# TIDA-01485_Page3.net
KiCad netlist of a schematic drawn in Altium Designer
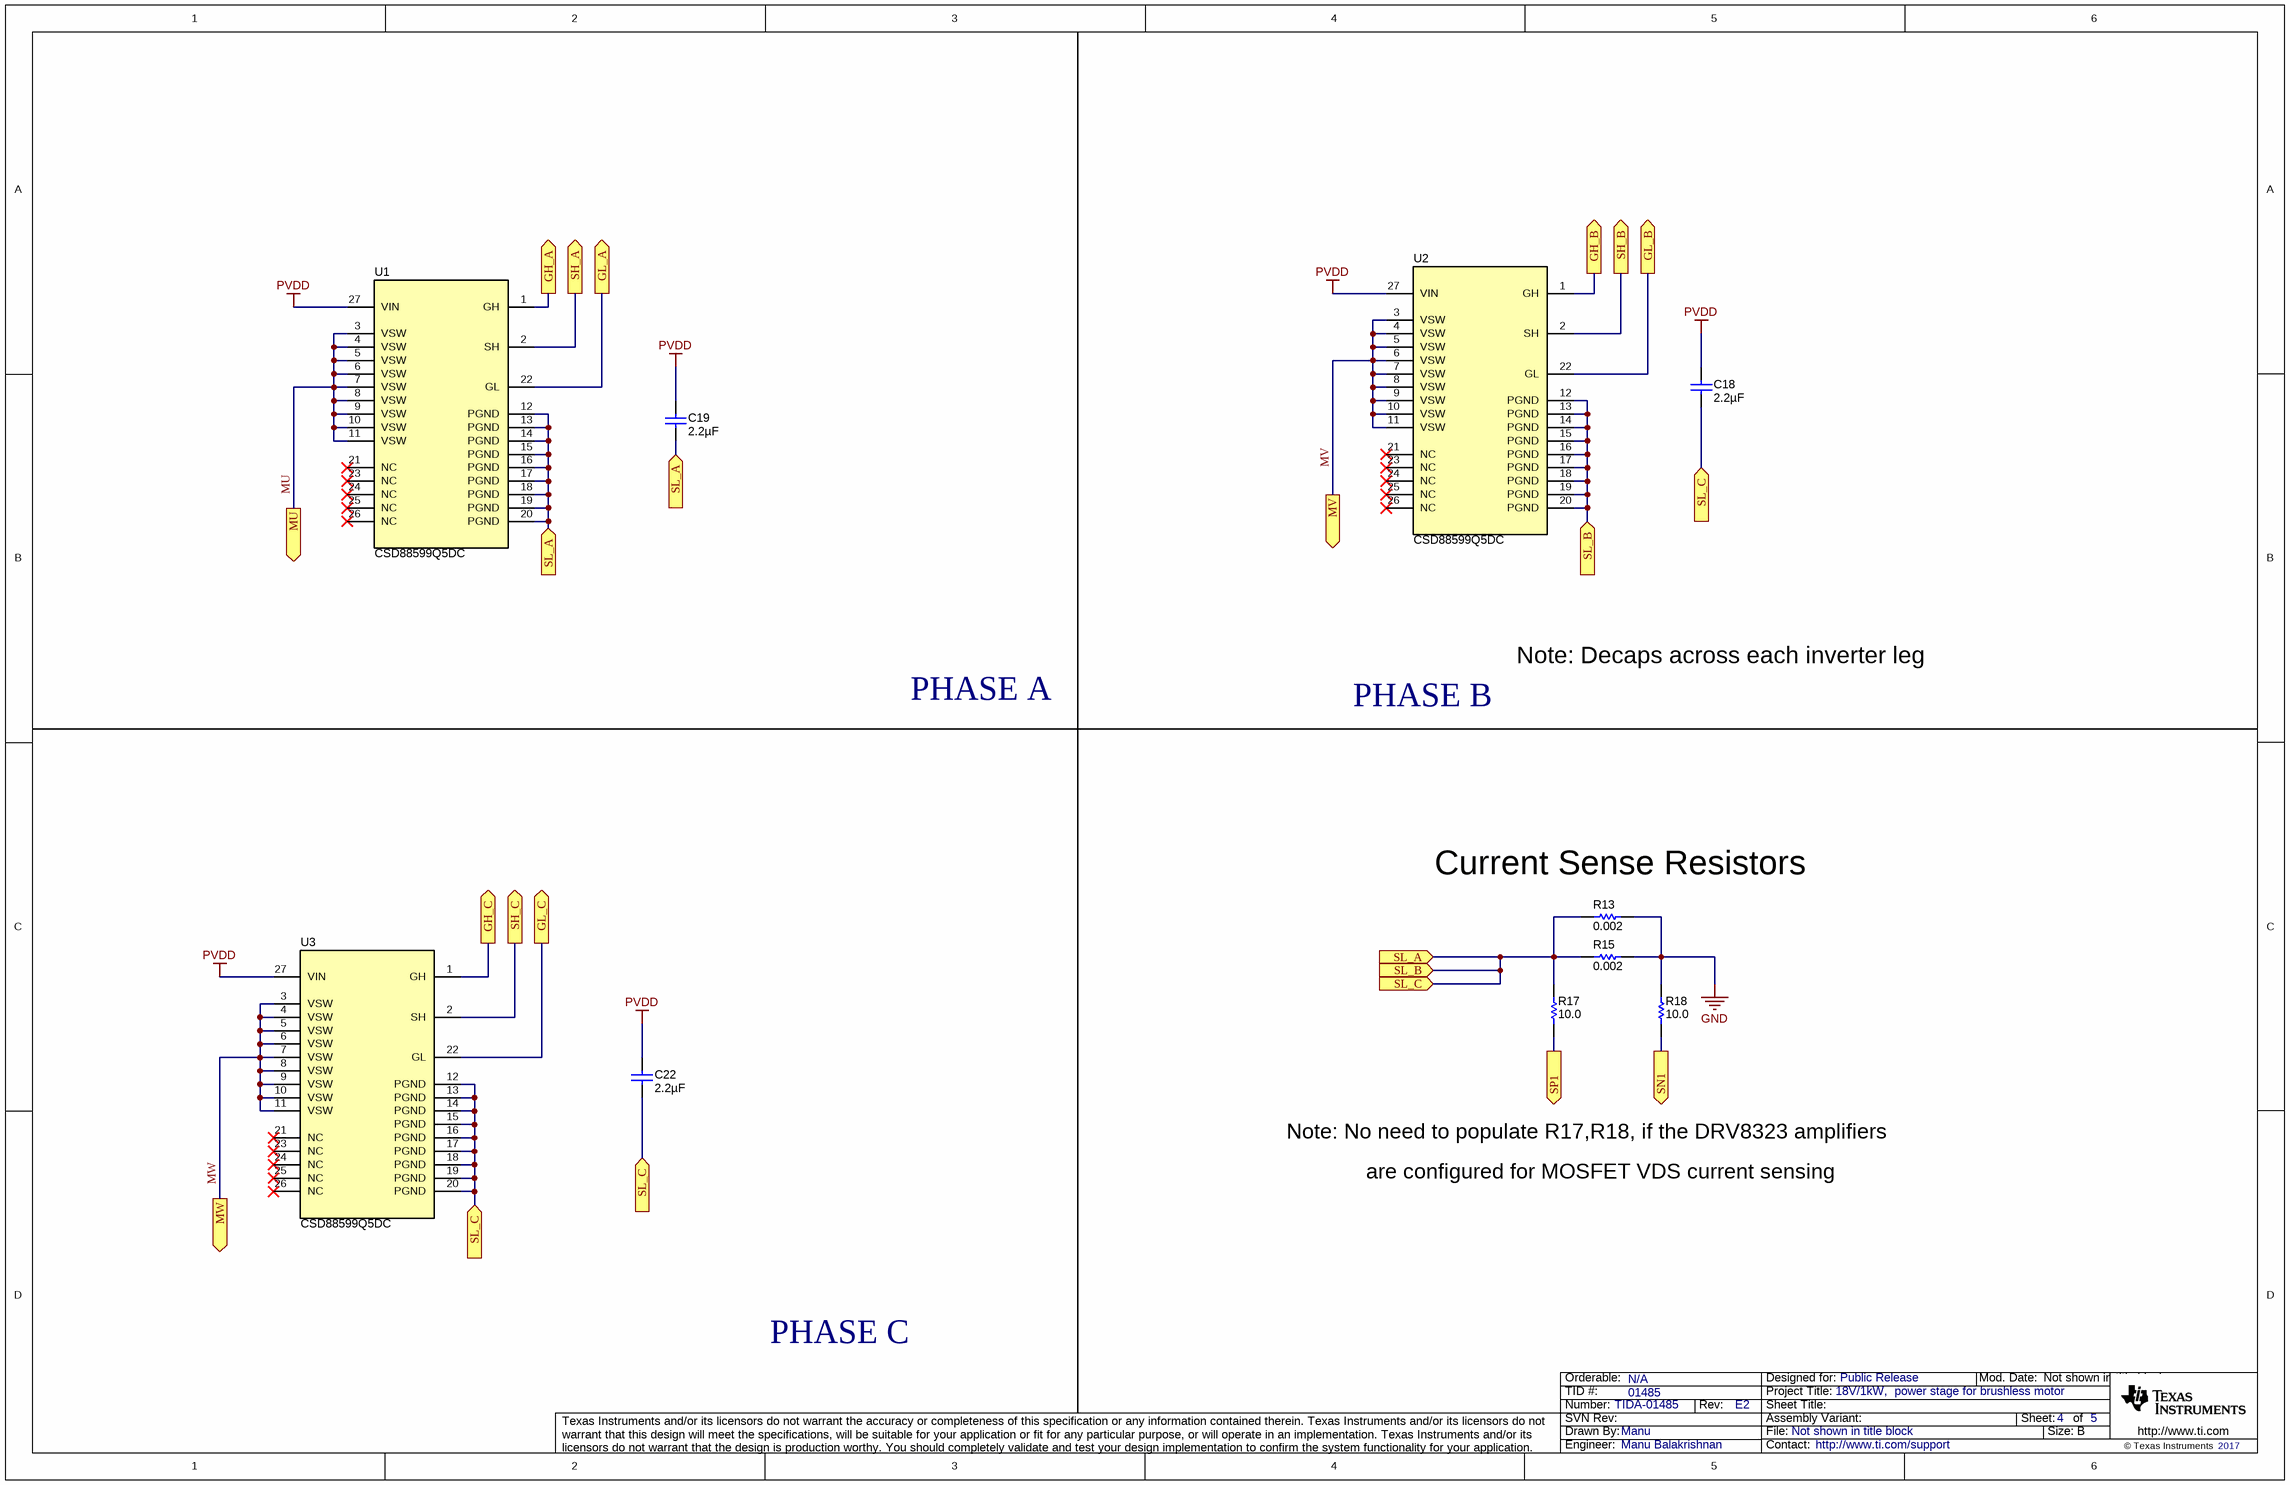
[diagram p0: TIDA-01485_Page3.SchDoc]

(export (version "E")
  (design (tool "Eeschema 10.0.6"))
  (components
    (comp (ref "C18")
      (value "GRM32ER72A225KA35L")
      (footprint "1210")
      (description "CAP, CERM, 2.2 µF, 100 V, +/- 10%, X7R, 1210")
      (fields
        (field (name "VALUEDISPLAYED") "2.2µF")
        (field (name "MANUFACTURER") "MuRata")
        (field (name "PUBLISHER") "Texas Instruments")
      )
      (libsource (lib "Capacitor_Ceramic") (part "GRM32ER72A225KA35L"))
    )
    (comp (ref "C19")
      (value "GRM32ER72A225KA35L")
      (footprint "1210")
      (description "CAP, CERM, 2.2 µF, 100 V, +/- 10%, X7R, 1210")
      (fields
        (field (name "VALUEDISPLAYED") "2.2µF")
        (field (name "MANUFACTURER") "MuRata")
        (field (name "PUBLISHER") "Texas Instruments")
      )
      (libsource (lib "Capacitor_Ceramic") (part "GRM32ER72A225KA35L"))
    )
    (comp (ref "C22")
      (value "GRM32ER72A225KA35L")
      (footprint "1210_270")
      (description "CAP, CERM, 2.2 µF, 100 V, +/- 10%, X7R, 1210")
      (fields
        (field (name "VALUEDISPLAYED") "2.2µF")
        (field (name "MANUFACTURER") "MuRata")
        (field (name "PUBLISHER") "Texas Instruments")
      )
      (libsource (lib "Capacitor_Ceramic") (part "GRM32ER72A225KA35L"))
    )
    (comp (ref "R13")
      (value "CRE2512-FZ-R002E-3")
      (footprint "CRE2512-R1_R4")
      (description "RES, 0.002, 1%, 3 W, AEC-Q200 Grade 0, 2512")
      (fields
        (field (name "VALUEDISPLAYED") "0.002")
        (field (name "MANUFACTURER") "Bourns")
        (field (name "PUBLISHER") "Texas Instruments")
      )
      (libsource (lib "Resistor_2512") (part "CRE2512-FZ-R002E-3"))
    )
    (comp (ref "R15")
      (value "CRE2512-FZ-R002E-3")
      (footprint "CRE2512-R1_R4")
      (description "RES, 0.002, 1%, 3 W, AEC-Q200 Grade 0, 2512")
      (fields
        (field (name "VALUEDISPLAYED") "0.002")
        (field (name "MANUFACTURER") "Bourns")
        (field (name "PUBLISHER") "Texas Instruments")
      )
      (libsource (lib "Resistor_2512") (part "CRE2512-FZ-R002E-3"))
    )
    (comp (ref "R17")
      (value "RMCF0402JT10R0")
      (footprint "0402")
      (description "RES, 10.0, 1%, 0.063 W, AEC-Q200 Grade 0, 0402")
      (fields
        (field (name "VALUEDISPLAYED") "10.0")
        (field (name "MANUFACTURER") "Stackpole Electronics Inc")
        (field (name "PUBLISHER") "Texas Instruments")
      )
      (libsource (lib "Resistor_0402") (part "RMCF0402JT10R0"))
    )
    (comp (ref "R18")
      (value "RMCF0402JT10R0")
      (footprint "0402")
      (description "RES, 10.0, 1%, 0.063 W, AEC-Q200 Grade 0, 0402")
      (fields
        (field (name "VALUEDISPLAYED") "10.0")
        (field (name "MANUFACTURER") "Stackpole Electronics Inc")
        (field (name "PUBLISHER") "Texas Instruments")
      )
      (libsource (lib "Resistor_0402") (part "RMCF0402JT10R0"))
    )
    (comp (ref "U1")
      (value "CSD88599Q5DC")
      (footprint "DMM0022A")
      (description "60 V Half-Bridge NexFE Power Block, DMM0022A")
      (fields
        (field (name "ALTERNATE PARTNUMBER") "CSD88599Q5DCT")
        (field (name "MANUFACTURER") "Texas Instruments")
        (field (name "SYMBOLCREATOR") "Altium")
        (field (name "PUBLISHER") "Texas Instruments")
      )
      (libsource (lib "TI_Pre_RTM") (part "CSD88599Q5DC"))
    )
    (comp (ref "U2")
      (value "CSD88599Q5DC")
      (footprint "DMM0022A")
      (description "60 V Half-Bridge NexFE Power Block, DMM0022A")
      (fields
        (field (name "ALTERNATE PARTNUMBER") "CSD88599Q5DCT")
        (field (name "MANUFACTURER") "Texas Instruments")
        (field (name "SYMBOLCREATOR") "Altium")
        (field (name "PUBLISHER") "Texas Instruments")
      )
      (libsource (lib "TI_Pre_RTM") (part "CSD88599Q5DC"))
    )
    (comp (ref "U3")
      (value "CSD88599Q5DC")
      (footprint "DMM0022A")
      (description "60 V Half-Bridge NexFE Power Block, DMM0022A")
      (fields
        (field (name "ALTERNATE PARTNUMBER") "CSD88599Q5DCT")
        (field (name "MANUFACTURER") "Texas Instruments")
        (field (name "SYMBOLCREATOR") "Altium")
        (field (name "PUBLISHER") "Texas Instruments")
      )
      (libsource (lib "TI_Pre_RTM") (part "CSD88599Q5DC"))
    )
  )
  (nets
    (net (code "1") (name "/GH_A") (class "Default")
      (node (ref "U1") (pin "1") (pinfunction "GH_1") (pintype "passive"))
    )
    (net (code "2") (name "/GH_B") (class "Default")
      (node (ref "U2") (pin "1") (pinfunction "GH_1") (pintype "passive"))
    )
    (net (code "3") (name "/GH_C") (class "Default")
      (node (ref "U3") (pin "1") (pinfunction "GH_1") (pintype "passive"))
    )
    (net (code "4") (name "/GL_A") (class "Default")
      (node (ref "U1") (pin "22") (pinfunction "GL_22") (pintype "passive"))
    )
    (net (code "5") (name "/GL_B") (class "Default")
      (node (ref "U2") (pin "22") (pinfunction "GL_22") (pintype "passive"))
    )
    (net (code "6") (name "/GL_C") (class "Default")
      (node (ref "U3") (pin "22") (pinfunction "GL_22") (pintype "passive"))
    )
    (net (code "7") (name "/MU") (class "Default")
      (node (ref "U1") (pin "10") (pinfunction "VSW_10") (pintype "passive"))
      (node (ref "U1") (pin "11") (pinfunction "VSW_11") (pintype "passive"))
      (node (ref "U1") (pin "3") (pinfunction "VSW_3") (pintype "passive"))
      (node (ref "U1") (pin "4") (pinfunction "VSW_4") (pintype "passive"))
      (node (ref "U1") (pin "5") (pinfunction "VSW_5") (pintype "passive"))
      (node (ref "U1") (pin "6") (pinfunction "VSW_6") (pintype "passive"))
      (node (ref "U1") (pin "7") (pinfunction "VSW_7") (pintype "passive"))
      (node (ref "U1") (pin "8") (pinfunction "VSW_8") (pintype "passive"))
      (node (ref "U1") (pin "9") (pinfunction "VSW_9") (pintype "passive"))
    )
    (net (code "8") (name "/MV") (class "Default")
      (node (ref "U2") (pin "10") (pinfunction "VSW_10") (pintype "passive"))
      (node (ref "U2") (pin "11") (pinfunction "VSW_11") (pintype "passive"))
      (node (ref "U2") (pin "3") (pinfunction "VSW_3") (pintype "passive"))
      (node (ref "U2") (pin "4") (pinfunction "VSW_4") (pintype "passive"))
      (node (ref "U2") (pin "5") (pinfunction "VSW_5") (pintype "passive"))
      (node (ref "U2") (pin "6") (pinfunction "VSW_6") (pintype "passive"))
      (node (ref "U2") (pin "7") (pinfunction "VSW_7") (pintype "passive"))
      (node (ref "U2") (pin "8") (pinfunction "VSW_8") (pintype "passive"))
      (node (ref "U2") (pin "9") (pinfunction "VSW_9") (pintype "passive"))
    )
    (net (code "9") (name "/MW") (class "Default")
      (node (ref "U3") (pin "10") (pinfunction "VSW_10") (pintype "passive"))
      (node (ref "U3") (pin "11") (pinfunction "VSW_11") (pintype "passive"))
      (node (ref "U3") (pin "3") (pinfunction "VSW_3") (pintype "passive"))
      (node (ref "U3") (pin "4") (pinfunction "VSW_4") (pintype "passive"))
      (node (ref "U3") (pin "5") (pinfunction "VSW_5") (pintype "passive"))
      (node (ref "U3") (pin "6") (pinfunction "VSW_6") (pintype "passive"))
      (node (ref "U3") (pin "7") (pinfunction "VSW_7") (pintype "passive"))
      (node (ref "U3") (pin "8") (pinfunction "VSW_8") (pintype "passive"))
      (node (ref "U3") (pin "9") (pinfunction "VSW_9") (pintype "passive"))
    )
    (net (code "10") (name "/SH_A") (class "Default")
      (node (ref "U1") (pin "2") (pinfunction "SH_2") (pintype "passive"))
    )
    (net (code "11") (name "/SH_B") (class "Default")
      (node (ref "U2") (pin "2") (pinfunction "SH_2") (pintype "passive"))
    )
    (net (code "12") (name "/SH_C") (class "Default")
      (node (ref "U3") (pin "2") (pinfunction "SH_2") (pintype "passive"))
    )
    (net (code "13") (name "/SL_A") (class "Default")
      (node (ref "C18") (pin "2") (pinfunction "2_2") (pintype "passive"))
      (node (ref "C19") (pin "2") (pinfunction "2_2") (pintype "passive"))
      (node (ref "C22") (pin "2") (pinfunction "2_2") (pintype "passive"))
      (node (ref "R13") (pin "1") (pinfunction "1_1") (pintype "passive"))
      (node (ref "R15") (pin "1") (pinfunction "1_1") (pintype "passive"))
      (node (ref "R17") (pin "2") (pinfunction "2_2") (pintype "passive"))
      (node (ref "U1") (pin "12") (pinfunction "PGND_12") (pintype "power_in"))
      (node (ref "U1") (pin "13") (pinfunction "PGND_13") (pintype "power_in"))
      (node (ref "U1") (pin "14") (pinfunction "PGND_14") (pintype "power_in"))
      (node (ref "U1") (pin "15") (pinfunction "PGND_15") (pintype "power_in"))
      (node (ref "U1") (pin "16") (pinfunction "PGND_16") (pintype "power_in"))
      (node (ref "U1") (pin "17") (pinfunction "PGND_17") (pintype "power_in"))
      (node (ref "U1") (pin "18") (pinfunction "PGND_18") (pintype "power_in"))
      (node (ref "U1") (pin "19") (pinfunction "PGND_19") (pintype "power_in"))
      (node (ref "U1") (pin "20") (pinfunction "PGND_20") (pintype "power_in"))
      (node (ref "U2") (pin "12") (pinfunction "PGND_12") (pintype "power_in"))
      (node (ref "U2") (pin "13") (pinfunction "PGND_13") (pintype "power_in"))
      (node (ref "U2") (pin "14") (pinfunction "PGND_14") (pintype "power_in"))
      (node (ref "U2") (pin "15") (pinfunction "PGND_15") (pintype "power_in"))
      (node (ref "U2") (pin "16") (pinfunction "PGND_16") (pintype "power_in"))
      (node (ref "U2") (pin "17") (pinfunction "PGND_17") (pintype "power_in"))
      (node (ref "U2") (pin "18") (pinfunction "PGND_18") (pintype "power_in"))
      (node (ref "U2") (pin "19") (pinfunction "PGND_19") (pintype "power_in"))
      (node (ref "U2") (pin "20") (pinfunction "PGND_20") (pintype "power_in"))
      (node (ref "U3") (pin "12") (pinfunction "PGND_12") (pintype "power_in"))
      (node (ref "U3") (pin "13") (pinfunction "PGND_13") (pintype "power_in"))
      (node (ref "U3") (pin "14") (pinfunction "PGND_14") (pintype "power_in"))
      (node (ref "U3") (pin "15") (pinfunction "PGND_15") (pintype "power_in"))
      (node (ref "U3") (pin "16") (pinfunction "PGND_16") (pintype "power_in"))
      (node (ref "U3") (pin "17") (pinfunction "PGND_17") (pintype "power_in"))
      (node (ref "U3") (pin "18") (pinfunction "PGND_18") (pintype "power_in"))
      (node (ref "U3") (pin "19") (pinfunction "PGND_19") (pintype "power_in"))
      (node (ref "U3") (pin "20") (pinfunction "PGND_20") (pintype "power_in"))
    )
    (net (code "14") (name "/SN1") (class "Default")
      (node (ref "R18") (pin "1") (pinfunction "1_1") (pintype "passive"))
    )
    (net (code "15") (name "/SP1") (class "Default")
      (node (ref "R17") (pin "1") (pinfunction "1_1") (pintype "passive"))
    )
    (net (code "16") (name "GND") (class "Default")
      (node (ref "R13") (pin "2") (pinfunction "2_2") (pintype "passive"))
      (node (ref "R15") (pin "2") (pinfunction "2_2") (pintype "passive"))
      (node (ref "R18") (pin "2") (pinfunction "2_2") (pintype "passive"))
    )
    (net (code "17") (name "PVDD") (class "Default")
      (node (ref "C18") (pin "1") (pinfunction "1_1") (pintype "passive"))
      (node (ref "C19") (pin "1") (pinfunction "1_1") (pintype "passive"))
      (node (ref "C22") (pin "1") (pinfunction "1_1") (pintype "passive"))
      (node (ref "U1") (pin "27") (pinfunction "VIN_27") (pintype "power_in"))
      (node (ref "U2") (pin "27") (pinfunction "VIN_27") (pintype "power_in"))
      (node (ref "U3") (pin "27") (pinfunction "VIN_27") (pintype "power_in"))
    )
    (net (code "18") (name "unconnected-(U1-NC-Pad21)") (class "Default")
      (node (ref "U1") (pin "21") (pinfunction "NC_21") (pintype "passive+no_connect"))
    )
    (net (code "19") (name "unconnected-(U1-NC-Pad23)") (class "Default")
      (node (ref "U1") (pin "23") (pinfunction "NC_23") (pintype "passive+no_connect"))
    )
    (net (code "20") (name "unconnected-(U1-NC-Pad24)") (class "Default")
      (node (ref "U1") (pin "24") (pinfunction "NC_24") (pintype "passive+no_connect"))
    )
    (net (code "21") (name "unconnected-(U1-NC-Pad25)") (class "Default")
      (node (ref "U1") (pin "25") (pinfunction "NC_25") (pintype "passive+no_connect"))
    )
    (net (code "22") (name "unconnected-(U1-NC-Pad26)") (class "Default")
      (node (ref "U1") (pin "26") (pinfunction "NC_26") (pintype "passive+no_connect"))
    )
    (net (code "23") (name "unconnected-(U2-NC-Pad21)") (class "Default")
      (node (ref "U2") (pin "21") (pinfunction "NC_21") (pintype "passive+no_connect"))
    )
    (net (code "24") (name "unconnected-(U2-NC-Pad23)") (class "Default")
      (node (ref "U2") (pin "23") (pinfunction "NC_23") (pintype "passive+no_connect"))
    )
    (net (code "25") (name "unconnected-(U2-NC-Pad24)") (class "Default")
      (node (ref "U2") (pin "24") (pinfunction "NC_24") (pintype "passive+no_connect"))
    )
    (net (code "26") (name "unconnected-(U2-NC-Pad25)") (class "Default")
      (node (ref "U2") (pin "25") (pinfunction "NC_25") (pintype "passive+no_connect"))
    )
    (net (code "27") (name "unconnected-(U2-NC-Pad26)") (class "Default")
      (node (ref "U2") (pin "26") (pinfunction "NC_26") (pintype "passive+no_connect"))
    )
    (net (code "28") (name "unconnected-(U3-NC-Pad21)") (class "Default")
      (node (ref "U3") (pin "21") (pinfunction "NC_21") (pintype "passive+no_connect"))
    )
    (net (code "29") (name "unconnected-(U3-NC-Pad23)") (class "Default")
      (node (ref "U3") (pin "23") (pinfunction "NC_23") (pintype "passive+no_connect"))
    )
    (net (code "30") (name "unconnected-(U3-NC-Pad24)") (class "Default")
      (node (ref "U3") (pin "24") (pinfunction "NC_24") (pintype "passive+no_connect"))
    )
    (net (code "31") (name "unconnected-(U3-NC-Pad25)") (class "Default")
      (node (ref "U3") (pin "25") (pinfunction "NC_25") (pintype "passive+no_connect"))
    )
    (net (code "32") (name "unconnected-(U3-NC-Pad26)") (class "Default")
      (node (ref "U3") (pin "26") (pinfunction "NC_26") (pintype "passive+no_connect"))
    )
  )
)
